# General_Switch_Board_V6.net
KiCad netlist of a schematic drawn in EAGLE
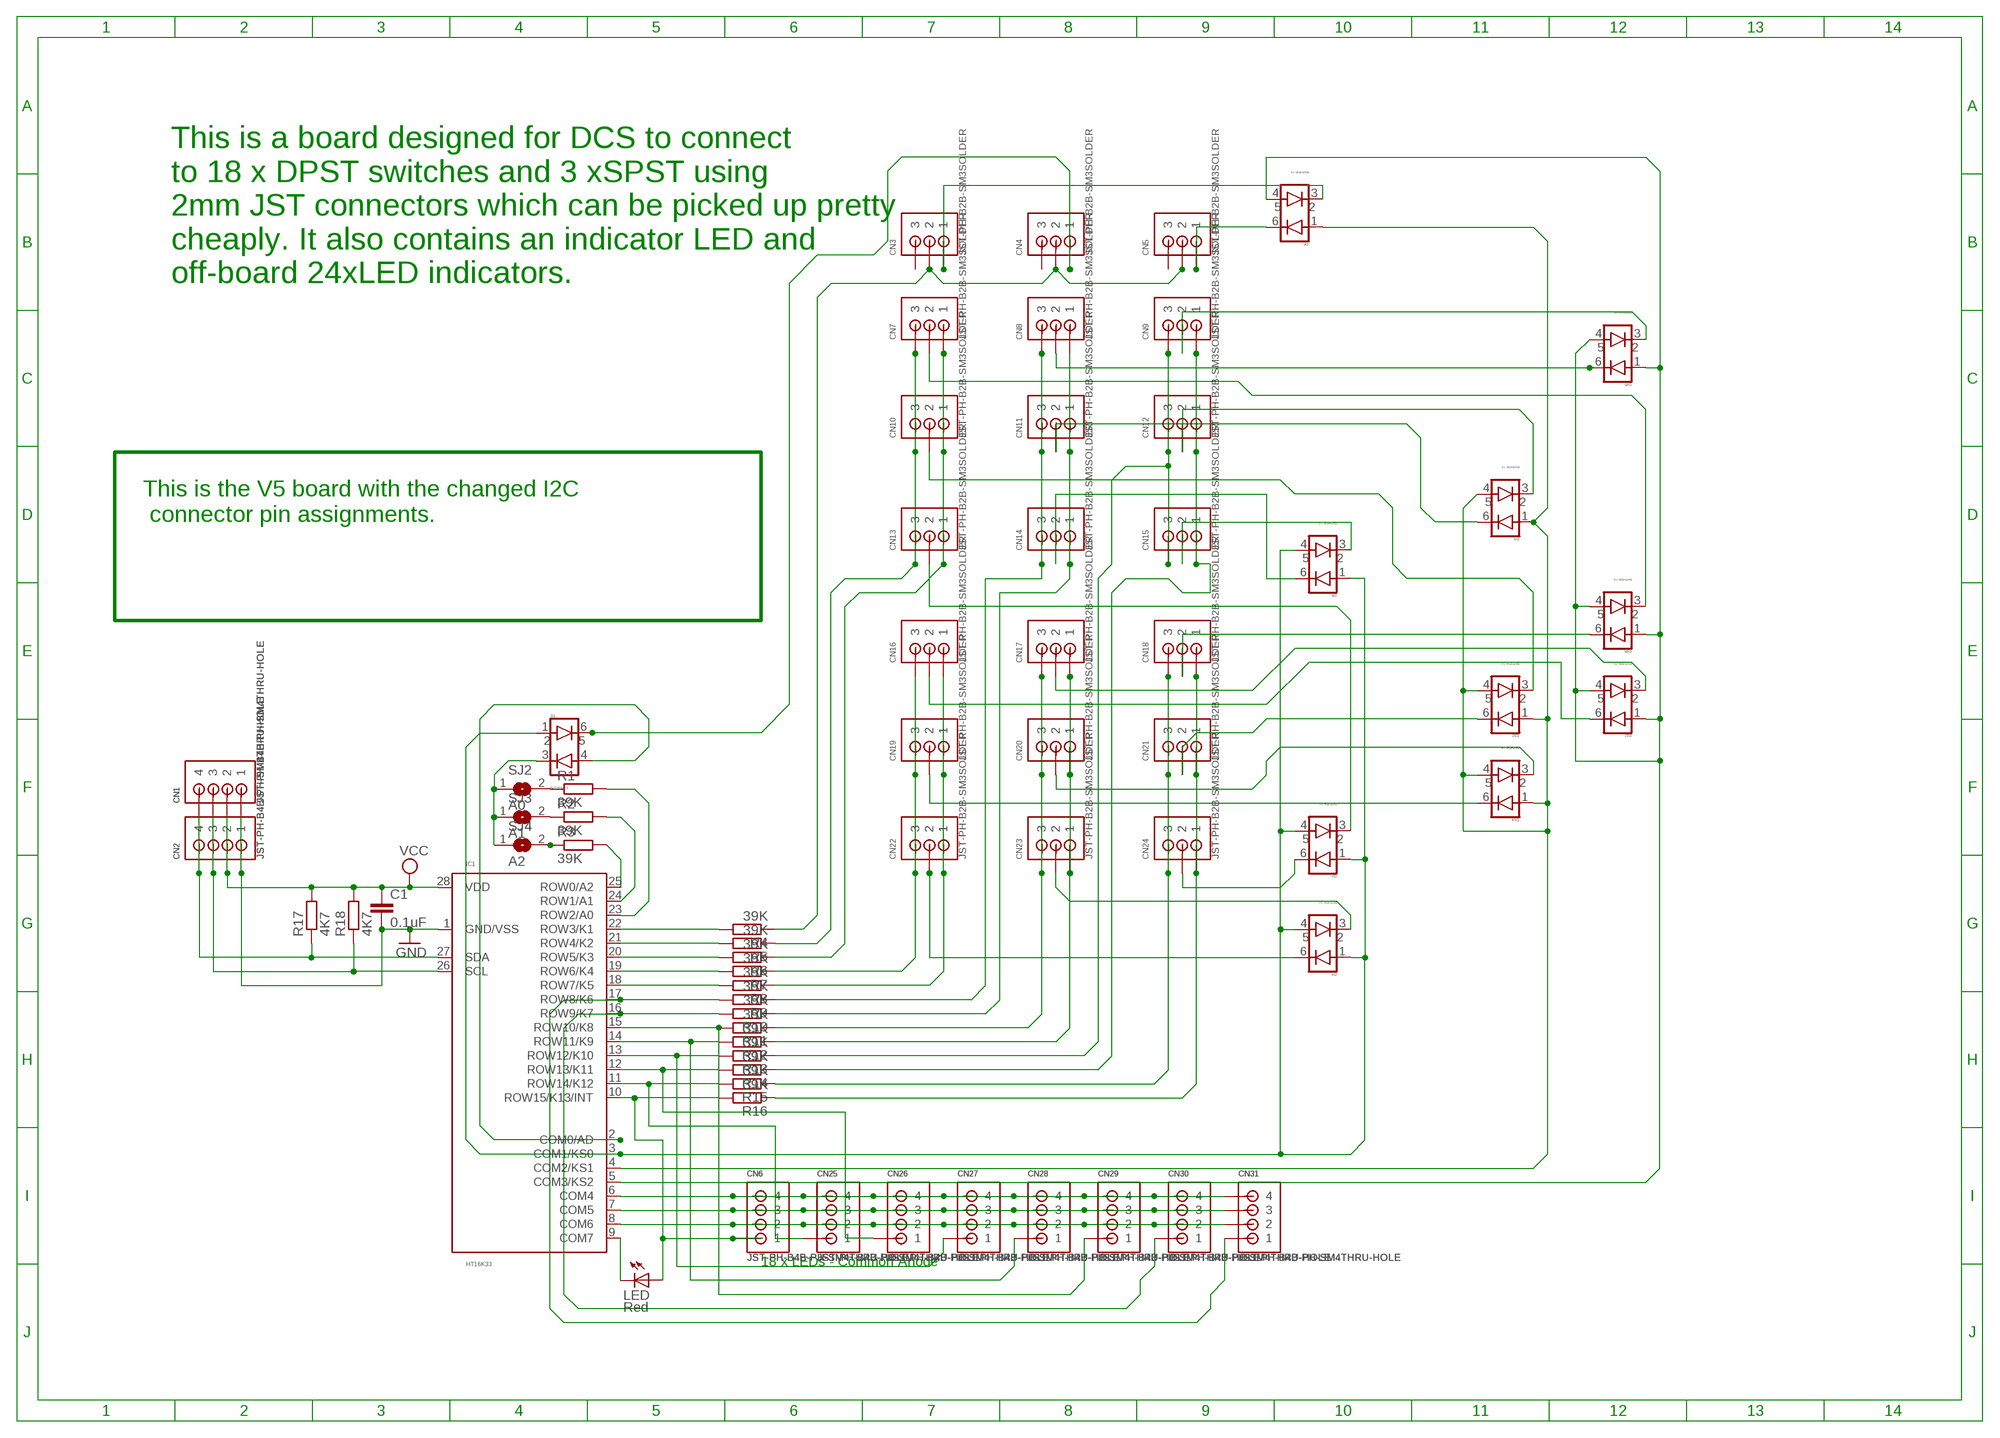
[diagram p0: schematic, sheet 1]

(export (version "E")
  (design (tool "Eeschema 10.0.6"))
  (components
    (comp (ref "C1")
      (value "0.1uF")
      (footprint "eagle-import:C0805")
      (libsource (lib "eagle-import") (part "C-EUC0805"))
    )
    (comp (ref "CN1")
      (value "JST-PH-B4B-PH-SM4THRU-HOLE")
      (footprint "eagle-import:B4B-PH-SOLDER")
      (libsource (lib "eagle-import") (part "JST-PH-B4B-PH-SM4THRU-HOLE"))
    )
    (comp (ref "CN2")
      (value "JST-PH-B4B-PH-SM4THRU-HOLE")
      (footprint "eagle-import:B4B-PH-SOLDER")
      (libsource (lib "eagle-import") (part "JST-PH-B4B-PH-SM4THRU-HOLE"))
    )
    (comp (ref "CN3")
      (value "JST-PH-B2B-SM3SOLDER")
      (footprint "eagle-import:B3B-PH-SOLDER")
      (libsource (lib "eagle-import") (part "JST-PH-B2B-SM3SOLDER"))
    )
    (comp (ref "CN4")
      (value "JST-PH-B2B-SM3SOLDER")
      (footprint "eagle-import:B3B-PH-SOLDER")
      (libsource (lib "eagle-import") (part "JST-PH-B2B-SM3SOLDER"))
    )
    (comp (ref "CN5")
      (value "JST-PH-B2B-SM3SOLDER")
      (footprint "eagle-import:B3B-PH-SOLDER")
      (libsource (lib "eagle-import") (part "JST-PH-B2B-SM3SOLDER"))
    )
    (comp (ref "CN6")
      (value "JST-PH-B4B-PH-SM4THRU-HOLE")
      (footprint "eagle-import:B4B-PH-SOLDER")
      (libsource (lib "eagle-import") (part "JST-PH-B4B-PH-SM4THRU-HOLE"))
    )
    (comp (ref "CN7")
      (value "JST-PH-B2B-SM3SOLDER")
      (footprint "eagle-import:B3B-PH-SOLDER")
      (libsource (lib "eagle-import") (part "JST-PH-B2B-SM3SOLDER"))
    )
    (comp (ref "CN8")
      (value "JST-PH-B2B-SM3SOLDER")
      (footprint "eagle-import:B3B-PH-SOLDER")
      (libsource (lib "eagle-import") (part "JST-PH-B2B-SM3SOLDER"))
    )
    (comp (ref "CN9")
      (value "JST-PH-B2B-SM3SOLDER")
      (footprint "eagle-import:B3B-PH-SOLDER")
      (libsource (lib "eagle-import") (part "JST-PH-B2B-SM3SOLDER"))
    )
    (comp (ref "CN10")
      (value "JST-PH-B2B-SM3SOLDER")
      (footprint "eagle-import:B3B-PH-SOLDER")
      (libsource (lib "eagle-import") (part "JST-PH-B2B-SM3SOLDER"))
    )
    (comp (ref "CN11")
      (value "JST-PH-B2B-SM3SOLDER")
      (footprint "eagle-import:B3B-PH-SOLDER")
      (libsource (lib "eagle-import") (part "JST-PH-B2B-SM3SOLDER"))
    )
    (comp (ref "CN12")
      (value "JST-PH-B2B-SM3SOLDER")
      (footprint "eagle-import:B3B-PH-SOLDER")
      (libsource (lib "eagle-import") (part "JST-PH-B2B-SM3SOLDER"))
    )
    (comp (ref "CN13")
      (value "JST-PH-B2B-SM3SOLDER")
      (footprint "eagle-import:B3B-PH-SOLDER")
      (libsource (lib "eagle-import") (part "JST-PH-B2B-SM3SOLDER"))
    )
    (comp (ref "CN14")
      (value "JST-PH-B2B-SM3SOLDER")
      (footprint "eagle-import:B3B-PH-SOLDER")
      (libsource (lib "eagle-import") (part "JST-PH-B2B-SM3SOLDER"))
    )
    (comp (ref "CN15")
      (value "JST-PH-B2B-SM3SOLDER")
      (footprint "eagle-import:B3B-PH-SOLDER")
      (libsource (lib "eagle-import") (part "JST-PH-B2B-SM3SOLDER"))
    )
    (comp (ref "CN16")
      (value "JST-PH-B2B-SM3SOLDER")
      (footprint "eagle-import:B3B-PH-SOLDER")
      (libsource (lib "eagle-import") (part "JST-PH-B2B-SM3SOLDER"))
    )
    (comp (ref "CN17")
      (value "JST-PH-B2B-SM3SOLDER")
      (footprint "eagle-import:B3B-PH-SOLDER")
      (libsource (lib "eagle-import") (part "JST-PH-B2B-SM3SOLDER"))
    )
    (comp (ref "CN18")
      (value "JST-PH-B2B-SM3SOLDER")
      (footprint "eagle-import:B3B-PH-SOLDER")
      (libsource (lib "eagle-import") (part "JST-PH-B2B-SM3SOLDER"))
    )
    (comp (ref "CN19")
      (value "JST-PH-B2B-SM3SOLDER")
      (footprint "eagle-import:B3B-PH-SOLDER")
      (libsource (lib "eagle-import") (part "JST-PH-B2B-SM3SOLDER"))
    )
    (comp (ref "CN20")
      (value "JST-PH-B2B-SM3SOLDER")
      (footprint "eagle-import:B3B-PH-SOLDER")
      (libsource (lib "eagle-import") (part "JST-PH-B2B-SM3SOLDER"))
    )
    (comp (ref "CN21")
      (value "JST-PH-B2B-SM3SOLDER")
      (footprint "eagle-import:B3B-PH-SOLDER")
      (libsource (lib "eagle-import") (part "JST-PH-B2B-SM3SOLDER"))
    )
    (comp (ref "CN22")
      (value "JST-PH-B2B-SM3SOLDER")
      (footprint "eagle-import:B3B-PH-SOLDER")
      (libsource (lib "eagle-import") (part "JST-PH-B2B-SM3SOLDER"))
    )
    (comp (ref "CN23")
      (value "JST-PH-B2B-SM3SOLDER")
      (footprint "eagle-import:B3B-PH-SOLDER")
      (libsource (lib "eagle-import") (part "JST-PH-B2B-SM3SOLDER"))
    )
    (comp (ref "CN24")
      (value "JST-PH-B2B-SM3SOLDER")
      (footprint "eagle-import:B3B-PH-SOLDER")
      (libsource (lib "eagle-import") (part "JST-PH-B2B-SM3SOLDER"))
    )
    (comp (ref "CN25")
      (value "JST-PH-B4B-PH-SM4THRU-HOLE")
      (footprint "eagle-import:B4B-PH-SOLDER")
      (libsource (lib "eagle-import") (part "JST-PH-B4B-PH-SM4THRU-HOLE"))
    )
    (comp (ref "CN26")
      (value "JST-PH-B4B-PH-SM4THRU-HOLE")
      (footprint "eagle-import:B4B-PH-SOLDER")
      (libsource (lib "eagle-import") (part "JST-PH-B4B-PH-SM4THRU-HOLE"))
    )
    (comp (ref "CN27")
      (value "JST-PH-B4B-PH-SM4THRU-HOLE")
      (footprint "eagle-import:B4B-PH-SOLDER")
      (libsource (lib "eagle-import") (part "JST-PH-B4B-PH-SM4THRU-HOLE"))
    )
    (comp (ref "CN28")
      (value "JST-PH-B4B-PH-SM4THRU-HOLE")
      (footprint "eagle-import:B4B-PH-SOLDER")
      (libsource (lib "eagle-import") (part "JST-PH-B4B-PH-SM4THRU-HOLE"))
    )
    (comp (ref "CN29")
      (value "JST-PH-B4B-PH-SM4THRU-HOLE")
      (footprint "eagle-import:B4B-PH-SOLDER")
      (libsource (lib "eagle-import") (part "JST-PH-B4B-PH-SM4THRU-HOLE"))
    )
    (comp (ref "CN30")
      (value "JST-PH-B4B-PH-SM4THRU-HOLE")
      (footprint "eagle-import:B4B-PH-SOLDER")
      (libsource (lib "eagle-import") (part "JST-PH-B4B-PH-SM4THRU-HOLE"))
    )
    (comp (ref "CN31")
      (value "JST-PH-B4B-PH-SM4THRU-HOLE")
      (footprint "eagle-import:B4B-PH-SOLDER")
      (libsource (lib "eagle-import") (part "JST-PH-B4B-PH-SM4THRU-HOLE"))
    )
    (comp (ref "D1")
      (value "BAT54TW-7-F")
      (footprint "eagle-import:SSOT6")
      (libsource (lib "eagle-import") (part "BAT54TW-7-F"))
    )
    (comp (ref "D2")
      (value "BAT54TW-7-F")
      (footprint "eagle-import:SSOT6")
      (libsource (lib "eagle-import") (part "BAT54TW-7-F"))
    )
    (comp (ref "D3")
      (value "BAT54TW-7-F")
      (footprint "eagle-import:SSOT6")
      (libsource (lib "eagle-import") (part "BAT54TW-7-F"))
    )
    (comp (ref "D4")
      (value "BAT54TW-7-F")
      (footprint "eagle-import:SSOT6")
      (libsource (lib "eagle-import") (part "BAT54TW-7-F"))
    )
    (comp (ref "D5")
      (value "BAT54TW-7-F")
      (footprint "eagle-import:SSOT6")
      (libsource (lib "eagle-import") (part "BAT54TW-7-F"))
    )
    (comp (ref "D6")
      (value "BAT54TW-7-F")
      (footprint "eagle-import:SSOT6")
      (libsource (lib "eagle-import") (part "BAT54TW-7-F"))
    )
    (comp (ref "D13")
      (value "BAT54TW-7-F")
      (footprint "eagle-import:SSOT6")
      (libsource (lib "eagle-import") (part "BAT54TW-7-F"))
    )
    (comp (ref "D14")
      (value "BAT54TW-7-F")
      (footprint "eagle-import:SSOT6")
      (libsource (lib "eagle-import") (part "BAT54TW-7-F"))
    )
    (comp (ref "D15")
      (value "BAT54TW-7-F")
      (footprint "eagle-import:SSOT6")
      (libsource (lib "eagle-import") (part "BAT54TW-7-F"))
    )
    (comp (ref "D16")
      (value "BAT54TW-7-F")
      (footprint "eagle-import:SSOT6")
      (libsource (lib "eagle-import") (part "BAT54TW-7-F"))
    )
    (comp (ref "D17")
      (value "BAT54TW-7-F")
      (footprint "eagle-import:SSOT6")
      (libsource (lib "eagle-import") (part "BAT54TW-7-F"))
    )
    (comp (ref "IC1")
      (value "HT16K33")
      (footprint "eagle-import:SOIC28")
      (libsource (lib "eagle-import") (part "HOLTEK_HT16K33"))
    )
    (comp (ref "LED")
      (value "Red")
      (footprint "eagle-import:CHIPLED_1206")
      (libsource (lib "eagle-import") (part "LEDCHIPLED_1206"))
    )
    (comp (ref "R1")
      (value "39K")
      (footprint "eagle-import:R0805")
      (libsource (lib "eagle-import") (part "resistor_R-EU_R0805"))
    )
    (comp (ref "R2")
      (value "39K")
      (footprint "eagle-import:R0805")
      (libsource (lib "eagle-import") (part "resistor_R-EU_R0805"))
    )
    (comp (ref "R3")
      (value "39K")
      (footprint "eagle-import:R0805")
      (libsource (lib "eagle-import") (part "resistor_R-EU_R0805"))
    )
    (comp (ref "R4")
      (value "39K")
      (footprint "eagle-import:R0805")
      (libsource (lib "eagle-import") (part "resistor_R-EU_R0805"))
    )
    (comp (ref "R5")
      (value "39K")
      (footprint "eagle-import:R0805")
      (libsource (lib "eagle-import") (part "resistor_R-EU_R0805"))
    )
    (comp (ref "R6")
      (value "39K")
      (footprint "eagle-import:R0805")
      (libsource (lib "eagle-import") (part "resistor_R-EU_R0805"))
    )
    (comp (ref "R7")
      (value "39K")
      (footprint "eagle-import:R0805")
      (libsource (lib "eagle-import") (part "resistor_R-EU_R0805"))
    )
    (comp (ref "R8")
      (value "39K")
      (footprint "eagle-import:R0805")
      (libsource (lib "eagle-import") (part "resistor_R-EU_R0805"))
    )
    (comp (ref "R9")
      (value "39K")
      (footprint "eagle-import:R0805")
      (libsource (lib "eagle-import") (part "resistor_R-EU_R0805"))
    )
    (comp (ref "R10")
      (value "39K")
      (footprint "eagle-import:R0805")
      (libsource (lib "eagle-import") (part "resistor_R-EU_R0805"))
    )
    (comp (ref "R11")
      (value "39K")
      (footprint "eagle-import:R0805")
      (libsource (lib "eagle-import") (part "resistor_R-EU_R0805"))
    )
    (comp (ref "R12")
      (value "39K")
      (footprint "eagle-import:R0805")
      (libsource (lib "eagle-import") (part "resistor_R-EU_R0805"))
    )
    (comp (ref "R13")
      (value "39K")
      (footprint "eagle-import:R0805")
      (libsource (lib "eagle-import") (part "resistor_R-EU_R0805"))
    )
    (comp (ref "R14")
      (value "39K")
      (footprint "eagle-import:R0805")
      (libsource (lib "eagle-import") (part "resistor_R-EU_R0805"))
    )
    (comp (ref "R15")
      (value "39K")
      (footprint "eagle-import:R0805")
      (libsource (lib "eagle-import") (part "resistor_R-EU_R0805"))
    )
    (comp (ref "R16")
      (value "39K")
      (footprint "eagle-import:R0805")
      (libsource (lib "eagle-import") (part "resistor_R-EU_R0805"))
    )
    (comp (ref "R17")
      (value "4K7")
      (footprint "eagle-import:R0805")
      (libsource (lib "eagle-import") (part "R-EU_R0805"))
    )
    (comp (ref "R18")
      (value "4K7")
      (footprint "eagle-import:R0805")
      (libsource (lib "eagle-import") (part "R-EU_R0805"))
    )
    (comp (ref "SJ2") (value "A0") (footprint "eagle-import:SJ") (libsource (lib "eagle-import") (part "SJ")))
    (comp (ref "SJ3") (value "A1") (footprint "eagle-import:SJ") (libsource (lib "eagle-import") (part "SJ")))
    (comp (ref "SJ4") (value "A2") (footprint "eagle-import:SJ") (libsource (lib "eagle-import") (part "SJ")))
  )
  (nets
    (net (code "1") (name "GND") (class "Default")
      (node (ref "C1") (pin "2") (pinfunction "2_2") (pintype "passive"))
      (node (ref "CN1") (pin "P1") (pinfunction "1_P1") (pintype "passive"))
      (node (ref "CN2") (pin "P1") (pinfunction "1_P1") (pintype "passive"))
      (node (ref "IC1") (pin "1") (pinfunction "GND/VSS_1") (pintype "power_in"))
    )
    (net (code "2") (name "Net-(CN1-3)") (class "Default")
      (node (ref "CN1") (pin "P3") (pinfunction "3_P3") (pintype "passive"))
      (node (ref "CN2") (pin "P3") (pinfunction "3_P3") (pintype "passive"))
      (node (ref "IC1") (pin "26") (pinfunction "SCL_26") (pintype "bidirectional"))
      (node (ref "R18") (pin "1") (pinfunction "1_1") (pintype "passive"))
    )
    (net (code "3") (name "Net-(CN1-4)") (class "Default")
      (node (ref "CN1") (pin "P4") (pinfunction "4_P4") (pintype "passive"))
      (node (ref "CN2") (pin "P4") (pinfunction "4_P4") (pintype "passive"))
      (node (ref "IC1") (pin "27") (pinfunction "SDA_27") (pintype "bidirectional"))
      (node (ref "R17") (pin "1") (pinfunction "1_1") (pintype "passive"))
    )
    (net (code "4") (name "Net-(CN3-1)") (class "Default")
      (node (ref "CN3") (pin "P1") (pinfunction "1_P1") (pintype "passive"))
      (node (ref "D6") (pin "3") (pinfunction "C2_3") (pintype "output"))
    )
    (net (code "5") (name "Net-(CN3-2)") (class "Default")
      (node (ref "CN3") (pin "P2") (pinfunction "2_P2") (pintype "passive"))
      (node (ref "CN4") (pin "P2") (pinfunction "2_P2") (pintype "passive"))
      (node (ref "CN5") (pin "P2") (pinfunction "2_P2") (pintype "passive"))
      (node (ref "R4") (pin "1") (pinfunction "1_1") (pintype "passive"))
    )
    (net (code "6") (name "Net-(CN4-1)") (class "Default")
      (node (ref "CN4") (pin "P1") (pinfunction "1_P1") (pintype "passive"))
      (node (ref "D1") (pin "6") (pinfunction "C1_6") (pintype "output"))
    )
    (net (code "7") (name "Net-(CN5-1)") (class "Default")
      (node (ref "CN5") (pin "P1") (pinfunction "1_P1") (pintype "passive"))
      (node (ref "D6") (pin "6") (pinfunction "C1_6") (pintype "output"))
    )
    (net (code "8") (name "Net-(CN6-1)") (class "Default")
      (node (ref "CN6") (pin "P1") (pinfunction "1_P1") (pintype "passive"))
      (node (ref "IC1") (pin "10") (pinfunction "ROW15/K13/INT_10") (pintype "input"))
      (node (ref "LED") (pin "A") (pinfunction "A_A") (pintype "passive"))
      (node (ref "R16") (pin "2") (pinfunction "2_2") (pintype "passive"))
    )
    (net (code "9") (name "Net-(CN7-2)") (class "Default")
      (node (ref "CN7") (pin "P2") (pinfunction "2_P2") (pintype "passive"))
      (node (ref "D16") (pin "3") (pinfunction "C2_3") (pintype "output"))
    )
    (net (code "10") (name "Net-(CN8-2)") (class "Default")
      (node (ref "CN8") (pin "P2") (pinfunction "2_P2") (pintype "passive"))
      (node (ref "D15") (pin "6") (pinfunction "C1_6") (pintype "output"))
    )
    (net (code "11") (name "Net-(CN9-2)") (class "Default")
      (node (ref "CN9") (pin "P2") (pinfunction "2_P2") (pintype "passive"))
      (node (ref "D15") (pin "3") (pinfunction "C2_3") (pintype "output"))
    )
    (net (code "12") (name "Net-(CN10-1)") (class "Default")
      (node (ref "CN10") (pin "P1") (pinfunction "1_P1") (pintype "passive"))
      (node (ref "CN13") (pin "P1") (pinfunction "1_P1") (pintype "passive"))
      (node (ref "CN7") (pin "P1") (pinfunction "1_P1") (pintype "passive"))
      (node (ref "R6") (pin "1") (pinfunction "1_1") (pintype "passive"))
    )
    (net (code "13") (name "Net-(CN10-2)") (class "Default")
      (node (ref "CN10") (pin "P2") (pinfunction "2_P2") (pintype "passive"))
      (node (ref "D13") (pin "3") (pinfunction "C2_3") (pintype "output"))
    )
    (net (code "14") (name "Net-(CN10-3)") (class "Default")
      (node (ref "CN10") (pin "P3") (pinfunction "3_P3") (pintype "passive"))
      (node (ref "CN13") (pin "P3") (pinfunction "3_P3") (pintype "passive"))
      (node (ref "CN7") (pin "P3") (pinfunction "3_P3") (pintype "passive"))
      (node (ref "R5") (pin "1") (pinfunction "1_1") (pintype "passive"))
    )
    (net (code "15") (name "Net-(CN11-1)") (class "Default")
      (node (ref "CN11") (pin "P1") (pinfunction "1_P1") (pintype "passive"))
      (node (ref "CN14") (pin "P1") (pinfunction "1_P1") (pintype "passive"))
      (node (ref "CN8") (pin "P1") (pinfunction "1_P1") (pintype "passive"))
      (node (ref "R10") (pin "1") (pinfunction "1_1") (pintype "passive"))
    )
    (net (code "16") (name "Net-(CN11-2)") (class "Default")
      (node (ref "CN11") (pin "P2") (pinfunction "2_P2") (pintype "passive"))
      (node (ref "D4") (pin "6") (pinfunction "C1_6") (pintype "output"))
    )
    (net (code "17") (name "Net-(CN11-3)") (class "Default")
      (node (ref "CN11") (pin "P3") (pinfunction "3_P3") (pintype "passive"))
      (node (ref "CN14") (pin "P3") (pinfunction "3_P3") (pintype "passive"))
      (node (ref "CN8") (pin "P3") (pinfunction "3_P3") (pintype "passive"))
      (node (ref "R9") (pin "1") (pinfunction "1_1") (pintype "passive"))
    )
    (net (code "18") (name "Net-(CN12-1)") (class "Default")
      (node (ref "CN12") (pin "P1") (pinfunction "1_P1") (pintype "passive"))
      (node (ref "CN15") (pin "P1") (pinfunction "1_P1") (pintype "passive"))
      (node (ref "CN9") (pin "P1") (pinfunction "1_P1") (pintype "passive"))
      (node (ref "R14") (pin "1") (pinfunction "1_1") (pintype "passive"))
    )
    (net (code "19") (name "Net-(CN12-2)") (class "Default")
      (node (ref "CN12") (pin "P2") (pinfunction "2_P2") (pintype "passive"))
      (node (ref "D4") (pin "3") (pinfunction "C2_3") (pintype "output"))
    )
    (net (code "20") (name "Net-(CN12-3)") (class "Default")
      (node (ref "CN12") (pin "P3") (pinfunction "3_P3") (pintype "passive"))
      (node (ref "CN15") (pin "P3") (pinfunction "3_P3") (pintype "passive"))
      (node (ref "CN9") (pin "P3") (pinfunction "3_P3") (pintype "passive"))
      (node (ref "R13") (pin "1") (pinfunction "1_1") (pintype "passive"))
    )
    (net (code "21") (name "Net-(CN13-2)") (class "Default")
      (node (ref "CN13") (pin "P2") (pinfunction "2_P2") (pintype "passive"))
      (node (ref "D2") (pin "3") (pinfunction "C2_3") (pintype "output"))
    )
    (net (code "22") (name "Net-(CN14-2)") (class "Default")
      (node (ref "CN14") (pin "P2") (pinfunction "2_P2") (pintype "passive"))
      (node (ref "D5") (pin "6") (pinfunction "C1_6") (pintype "output"))
    )
    (net (code "23") (name "Net-(CN15-2)") (class "Default")
      (node (ref "CN15") (pin "P2") (pinfunction "2_P2") (pintype "passive"))
      (node (ref "D5") (pin "3") (pinfunction "C2_3") (pintype "output"))
    )
    (net (code "24") (name "Net-(CN16-1)") (class "Default")
      (node (ref "CN16") (pin "P1") (pinfunction "1_P1") (pintype "passive"))
      (node (ref "CN19") (pin "P1") (pinfunction "1_P1") (pintype "passive"))
      (node (ref "CN22") (pin "P1") (pinfunction "1_P1") (pintype "passive"))
      (node (ref "R8") (pin "1") (pinfunction "1_1") (pintype "passive"))
    )
    (net (code "25") (name "Net-(CN16-2)") (class "Default")
      (node (ref "CN16") (pin "P2") (pinfunction "2_P2") (pintype "passive"))
      (node (ref "D17") (pin "6") (pinfunction "C1_6") (pintype "output"))
    )
    (net (code "26") (name "Net-(CN16-3)") (class "Default")
      (node (ref "CN16") (pin "P3") (pinfunction "3_P3") (pintype "passive"))
      (node (ref "CN19") (pin "P3") (pinfunction "3_P3") (pintype "passive"))
      (node (ref "CN22") (pin "P3") (pinfunction "3_P3") (pintype "passive"))
      (node (ref "R7") (pin "1") (pinfunction "1_1") (pintype "passive"))
    )
    (net (code "27") (name "Net-(CN17-1)") (class "Default")
      (node (ref "CN17") (pin "P1") (pinfunction "1_P1") (pintype "passive"))
      (node (ref "CN20") (pin "P1") (pinfunction "1_P1") (pintype "passive"))
      (node (ref "CN23") (pin "P1") (pinfunction "1_P1") (pintype "passive"))
      (node (ref "R12") (pin "1") (pinfunction "1_1") (pintype "passive"))
    )
    (net (code "28") (name "Net-(CN17-2)") (class "Default")
      (node (ref "CN17") (pin "P2") (pinfunction "2_P2") (pintype "passive"))
      (node (ref "D17") (pin "3") (pinfunction "C2_3") (pintype "output"))
    )
    (net (code "29") (name "Net-(CN17-3)") (class "Default")
      (node (ref "CN17") (pin "P3") (pinfunction "3_P3") (pintype "passive"))
      (node (ref "CN20") (pin "P3") (pinfunction "3_P3") (pintype "passive"))
      (node (ref "CN23") (pin "P3") (pinfunction "3_P3") (pintype "passive"))
      (node (ref "R11") (pin "1") (pinfunction "1_1") (pintype "passive"))
    )
    (net (code "30") (name "Net-(CN18-1)") (class "Default")
      (node (ref "CN18") (pin "P1") (pinfunction "1_P1") (pintype "passive"))
      (node (ref "CN21") (pin "P1") (pinfunction "1_P1") (pintype "passive"))
      (node (ref "CN24") (pin "P1") (pinfunction "1_P1") (pintype "passive"))
      (node (ref "R16") (pin "1") (pinfunction "1_1") (pintype "passive"))
    )
    (net (code "31") (name "Net-(CN18-2)") (class "Default")
      (node (ref "CN18") (pin "P2") (pinfunction "2_P2") (pintype "passive"))
      (node (ref "D16") (pin "6") (pinfunction "C1_6") (pintype "output"))
    )
    (net (code "32") (name "Net-(CN18-3)") (class "Default")
      (node (ref "CN18") (pin "P3") (pinfunction "3_P3") (pintype "passive"))
      (node (ref "CN21") (pin "P3") (pinfunction "3_P3") (pintype "passive"))
      (node (ref "CN24") (pin "P3") (pinfunction "3_P3") (pintype "passive"))
      (node (ref "R15") (pin "1") (pinfunction "1_1") (pintype "passive"))
    )
    (net (code "33") (name "Net-(CN19-2)") (class "Default")
      (node (ref "CN19") (pin "P2") (pinfunction "2_P2") (pintype "passive"))
      (node (ref "D14") (pin "6") (pinfunction "C1_6") (pintype "output"))
    )
    (net (code "34") (name "Net-(CN20-2)") (class "Default")
      (node (ref "CN20") (pin "P2") (pinfunction "2_P2") (pintype "passive"))
      (node (ref "D14") (pin "3") (pinfunction "C2_3") (pintype "output"))
    )
    (net (code "35") (name "Net-(CN21-2)") (class "Default")
      (node (ref "CN21") (pin "P2") (pinfunction "2_P2") (pintype "passive"))
      (node (ref "D13") (pin "6") (pinfunction "C1_6") (pintype "output"))
    )
    (net (code "36") (name "Net-(CN22-2)") (class "Default")
      (node (ref "CN22") (pin "P2") (pinfunction "2_P2") (pintype "passive"))
      (node (ref "D3") (pin "6") (pinfunction "C1_6") (pintype "output"))
    )
    (net (code "37") (name "Net-(CN23-2)") (class "Default")
      (node (ref "CN23") (pin "P2") (pinfunction "2_P2") (pintype "passive"))
      (node (ref "D3") (pin "3") (pinfunction "C2_3") (pintype "output"))
    )
    (net (code "38") (name "Net-(CN24-2)") (class "Default")
      (node (ref "CN24") (pin "P2") (pinfunction "2_P2") (pintype "passive"))
      (node (ref "D2") (pin "6") (pinfunction "C1_6") (pintype "output"))
    )
    (net (code "39") (name "Net-(CN25-1)") (class "Default")
      (node (ref "CN25") (pin "P1") (pinfunction "1_P1") (pintype "passive"))
      (node (ref "IC1") (pin "11") (pinfunction "ROW14/K12_11") (pintype "input"))
      (node (ref "R15") (pin "2") (pinfunction "2_2") (pintype "passive"))
    )
    (net (code "40") (name "Net-(CN25-2)") (class "Default")
      (node (ref "CN25") (pin "P2") (pinfunction "2_P2") (pintype "passive"))
      (node (ref "CN26") (pin "P2") (pinfunction "2_P2") (pintype "passive"))
      (node (ref "CN27") (pin "P2") (pinfunction "2_P2") (pintype "passive"))
      (node (ref "CN28") (pin "P2") (pinfunction "2_P2") (pintype "passive"))
      (node (ref "CN29") (pin "P2") (pinfunction "2_P2") (pintype "passive"))
      (node (ref "CN30") (pin "P2") (pinfunction "2_P2") (pintype "passive"))
      (node (ref "CN31") (pin "P2") (pinfunction "2_P2") (pintype "passive"))
      (node (ref "CN6") (pin "P2") (pinfunction "2_P2") (pintype "passive"))
      (node (ref "IC1") (pin "8") (pinfunction "COM6_8") (pintype "input"))
    )
    (net (code "41") (name "Net-(CN25-3)") (class "Default")
      (node (ref "CN25") (pin "P3") (pinfunction "3_P3") (pintype "passive"))
      (node (ref "CN26") (pin "P3") (pinfunction "3_P3") (pintype "passive"))
      (node (ref "CN27") (pin "P3") (pinfunction "3_P3") (pintype "passive"))
      (node (ref "CN28") (pin "P3") (pinfunction "3_P3") (pintype "passive"))
      (node (ref "CN29") (pin "P3") (pinfunction "3_P3") (pintype "passive"))
      (node (ref "CN30") (pin "P3") (pinfunction "3_P3") (pintype "passive"))
      (node (ref "CN31") (pin "P3") (pinfunction "3_P3") (pintype "passive"))
      (node (ref "CN6") (pin "P3") (pinfunction "3_P3") (pintype "passive"))
      (node (ref "IC1") (pin "7") (pinfunction "COM5_7") (pintype "input"))
    )
    (net (code "42") (name "Net-(CN25-4)") (class "Default")
      (node (ref "CN25") (pin "P4") (pinfunction "4_P4") (pintype "passive"))
      (node (ref "CN26") (pin "P4") (pinfunction "4_P4") (pintype "passive"))
      (node (ref "CN27") (pin "P4") (pinfunction "4_P4") (pintype "passive"))
      (node (ref "CN28") (pin "P4") (pinfunction "4_P4") (pintype "passive"))
      (node (ref "CN29") (pin "P4") (pinfunction "4_P4") (pintype "passive"))
      (node (ref "CN30") (pin "P4") (pinfunction "4_P4") (pintype "passive"))
      (node (ref "CN31") (pin "P4") (pinfunction "4_P4") (pintype "passive"))
      (node (ref "CN6") (pin "P4") (pinfunction "4_P4") (pintype "passive"))
      (node (ref "IC1") (pin "6") (pinfunction "COM4_6") (pintype "input"))
    )
    (net (code "43") (name "Net-(CN26-1)") (class "Default")
      (node (ref "CN26") (pin "P1") (pinfunction "1_P1") (pintype "passive"))
      (node (ref "IC1") (pin "12") (pinfunction "ROW13/K11_12") (pintype "input"))
      (node (ref "R14") (pin "2") (pinfunction "2_2") (pintype "passive"))
    )
    (net (code "44") (name "Net-(CN27-1)") (class "Default")
      (node (ref "CN27") (pin "P1") (pinfunction "1_P1") (pintype "passive"))
      (node (ref "IC1") (pin "13") (pinfunction "ROW12/K10_13") (pintype "input"))
      (node (ref "R13") (pin "2") (pinfunction "2_2") (pintype "passive"))
    )
    (net (code "45") (name "Net-(CN28-1)") (class "Default")
      (node (ref "CN28") (pin "P1") (pinfunction "1_P1") (pintype "passive"))
      (node (ref "IC1") (pin "14") (pinfunction "ROW11/K9_14") (pintype "input"))
      (node (ref "R12") (pin "2") (pinfunction "2_2") (pintype "passive"))
    )
    (net (code "46") (name "Net-(CN29-1)") (class "Default")
      (node (ref "CN29") (pin "P1") (pinfunction "1_P1") (pintype "passive"))
      (node (ref "IC1") (pin "15") (pinfunction "ROW10/K8_15") (pintype "input"))
      (node (ref "R11") (pin "2") (pinfunction "2_2") (pintype "passive"))
    )
    (net (code "47") (name "Net-(CN30-1)") (class "Default")
      (node (ref "CN30") (pin "P1") (pinfunction "1_P1") (pintype "passive"))
      (node (ref "IC1") (pin "16") (pinfunction "ROW9/K7_16") (pintype "bidirectional"))
      (node (ref "R10") (pin "2") (pinfunction "2_2") (pintype "passive"))
    )
    (net (code "48") (name "Net-(CN31-1)") (class "Default")
      (node (ref "CN31") (pin "P1") (pinfunction "1_P1") (pintype "passive"))
      (node (ref "IC1") (pin "17") (pinfunction "ROW8/K6_17") (pintype "input"))
      (node (ref "R9") (pin "2") (pinfunction "2_2") (pintype "passive"))
    )
    (net (code "49") (name "Net-(D1-A1)") (class "Default")
      (node (ref "D1") (pin "1") (pinfunction "A1_1") (pintype "input"))
      (node (ref "D2") (pin "1") (pinfunction "A1_1") (pintype "input"))
      (node (ref "D2") (pin "4") (pinfunction "A2_4") (pintype "input"))
      (node (ref "D3") (pin "1") (pinfunction "A1_1") (pintype "input"))
      (node (ref "D3") (pin "4") (pinfunction "A2_4") (pintype "input"))
      (node (ref "D5") (pin "1") (pinfunction "A1_1") (pintype "input"))
      (node (ref "D5") (pin "4") (pinfunction "A2_4") (pintype "input"))
      (node (ref "IC1") (pin "3") (pinfunction "COM1/KS0_3") (pintype "input"))
    )
    (net (code "50") (name "Net-(D1-A2)") (class "Default")
      (node (ref "D1") (pin "4") (pinfunction "A2_4") (pintype "input"))
      (node (ref "IC1") (pin "2") (pinfunction "COM0/AD_2") (pintype "input"))
    )
    (net (code "51") (name "Net-(D1-C2)") (class "Default")
      (node (ref "D1") (pin "3") (pinfunction "C2_3") (pintype "output"))
      (node (ref "SJ2") (pin "1") (pinfunction "1_1") (pintype "passive"))
      (node (ref "SJ3") (pin "1") (pinfunction "1_1") (pintype "passive"))
      (node (ref "SJ4") (pin "1") (pinfunction "1_1") (pintype "passive"))
    )
    (net (code "52") (name "Net-(D13-A1)") (class "Default")
      (node (ref "D13") (pin "1") (pinfunction "A1_1") (pintype "input"))
      (node (ref "D13") (pin "4") (pinfunction "A2_4") (pintype "input"))
      (node (ref "D14") (pin "1") (pinfunction "A1_1") (pintype "input"))
      (node (ref "D14") (pin "4") (pinfunction "A2_4") (pintype "input"))
      (node (ref "D4") (pin "1") (pinfunction "A1_1") (pintype "input"))
      (node (ref "D4") (pin "4") (pinfunction "A2_4") (pintype "input"))
      (node (ref "D6") (pin "1") (pinfunction "A1_1") (pintype "input"))
      (node (ref "IC1") (pin "4") (pinfunction "COM2/KS1_4") (pintype "input"))
    )
    (net (code "53") (name "Net-(D15-A1)") (class "Default")
      (node (ref "D15") (pin "1") (pinfunction "A1_1") (pintype "input"))
      (node (ref "D15") (pin "4") (pinfunction "A2_4") (pintype "input"))
      (node (ref "D16") (pin "1") (pinfunction "A1_1") (pintype "input"))
      (node (ref "D16") (pin "4") (pinfunction "A2_4") (pintype "input"))
      (node (ref "D17") (pin "1") (pinfunction "A1_1") (pintype "input"))
      (node (ref "D17") (pin "4") (pinfunction "A2_4") (pintype "input"))
      (node (ref "D6") (pin "4") (pinfunction "A2_4") (pintype "input"))
      (node (ref "IC1") (pin "5") (pinfunction "COM3/KS2_5") (pintype "input"))
    )
    (net (code "54") (name "Net-(IC1-COM7)") (class "Default")
      (node (ref "IC1") (pin "9") (pinfunction "COM7_9") (pintype "input"))
      (node (ref "LED") (pin "C") (pinfunction "C_C") (pintype "passive"))
    )
    (net (code "55") (name "Net-(IC1-ROW0{slash}A2)") (class "Default")
      (node (ref "IC1") (pin "25") (pinfunction "ROW0/A2_25") (pintype "bidirectional"))
      (node (ref "R3") (pin "2") (pinfunction "2_2") (pintype "passive"))
    )
    (net (code "56") (name "Net-(IC1-ROW1{slash}A1)") (class "Default")
      (node (ref "IC1") (pin "24") (pinfunction "ROW1/A1_24") (pintype "bidirectional"))
      (node (ref "R2") (pin "2") (pinfunction "2_2") (pintype "passive"))
    )
    (net (code "57") (name "Net-(IC1-ROW2{slash}A0)") (class "Default")
      (node (ref "IC1") (pin "23") (pinfunction "ROW2/A0_23") (pintype "bidirectional"))
      (node (ref "R1") (pin "2") (pinfunction "2_2") (pintype "passive"))
    )
    (net (code "58") (name "Net-(IC1-ROW3{slash}K1)") (class "Default")
      (node (ref "IC1") (pin "22") (pinfunction "ROW3/K1_22") (pintype "bidirectional"))
      (node (ref "R4") (pin "2") (pinfunction "2_2") (pintype "passive"))
    )
    (net (code "59") (name "Net-(IC1-ROW4{slash}K2)") (class "Default")
      (node (ref "IC1") (pin "21") (pinfunction "ROW4/K2_21") (pintype "input"))
      (node (ref "R5") (pin "2") (pinfunction "2_2") (pintype "passive"))
    )
    (net (code "60") (name "Net-(IC1-ROW5{slash}K3)") (class "Default")
      (node (ref "IC1") (pin "20") (pinfunction "ROW5/K3_20") (pintype "bidirectional"))
      (node (ref "R6") (pin "2") (pinfunction "2_2") (pintype "passive"))
    )
    (net (code "61") (name "Net-(IC1-ROW6{slash}K4)") (class "Default")
      (node (ref "IC1") (pin "19") (pinfunction "ROW6/K4_19") (pintype "bidirectional"))
      (node (ref "R7") (pin "2") (pinfunction "2_2") (pintype "passive"))
    )
    (net (code "62") (name "Net-(IC1-ROW7{slash}K5)") (class "Default")
      (node (ref "IC1") (pin "18") (pinfunction "ROW7/K5_18") (pintype "bidirectional"))
      (node (ref "R8") (pin "2") (pinfunction "2_2") (pintype "passive"))
    )
    (net (code "63") (name "Net-(R1-Pad1)") (class "Default")
      (node (ref "R1") (pin "1") (pinfunction "1_1") (pintype "passive"))
      (node (ref "SJ2") (pin "2") (pinfunction "2_2") (pintype "passive"))
    )
    (net (code "64") (name "Net-(R2-Pad1)") (class "Default")
      (node (ref "R2") (pin "1") (pinfunction "1_1") (pintype "passive"))
      (node (ref "SJ3") (pin "2") (pinfunction "2_2") (pintype "passive"))
    )
    (net (code "65") (name "Net-(R3-Pad1)") (class "Default")
      (node (ref "R3") (pin "1") (pinfunction "1_1") (pintype "passive"))
      (node (ref "SJ4") (pin "2") (pinfunction "2_2") (pintype "passive"))
    )
    (net (code "66") (name "VCC") (class "Default")
      (node (ref "C1") (pin "1") (pinfunction "1_1") (pintype "passive"))
      (node (ref "CN1") (pin "P2") (pinfunction "2_P2") (pintype "passive"))
      (node (ref "CN2") (pin "P2") (pinfunction "2_P2") (pintype "passive"))
      (node (ref "IC1") (pin "28") (pinfunction "VDD_28") (pintype "power_in"))
      (node (ref "R17") (pin "2") (pinfunction "2_2") (pintype "passive"))
      (node (ref "R18") (pin "2") (pinfunction "2_2") (pintype "passive"))
    )
    (net (code "67") (name "unconnected-(CN3-3-PadP3)") (class "Default")
      (node (ref "CN3") (pin "P3") (pinfunction "3_P3") (pintype "passive"))
    )
    (net (code "68") (name "unconnected-(CN4-3-PadP3)") (class "Default")
      (node (ref "CN4") (pin "P3") (pinfunction "3_P3") (pintype "passive"))
    )
    (net (code "69") (name "unconnected-(CN5-3-PadP3)") (class "Default")
      (node (ref "CN5") (pin "P3") (pinfunction "3_P3") (pintype "passive"))
    )
    (net (code "70") (name "unconnected-(D1-NC0-Pad2)") (class "Default")
      (node (ref "D1") (pin "2") (pinfunction "NC0_2") (pintype "no_connect"))
    )
    (net (code "71") (name "unconnected-(D1-NC1-Pad5)") (class "Default")
      (node (ref "D1") (pin "5") (pinfunction "NC1_5") (pintype "no_connect"))
    )
    (net (code "72") (name "unconnected-(D2-NC0-Pad2)") (class "Default")
      (node (ref "D2") (pin "2") (pinfunction "NC0_2") (pintype "no_connect"))
    )
    (net (code "73") (name "unconnected-(D2-NC1-Pad5)") (class "Default")
      (node (ref "D2") (pin "5") (pinfunction "NC1_5") (pintype "no_connect"))
    )
    (net (code "74") (name "unconnected-(D3-NC0-Pad2)") (class "Default")
      (node (ref "D3") (pin "2") (pinfunction "NC0_2") (pintype "no_connect"))
    )
    (net (code "75") (name "unconnected-(D3-NC1-Pad5)") (class "Default")
      (node (ref "D3") (pin "5") (pinfunction "NC1_5") (pintype "no_connect"))
    )
    (net (code "76") (name "unconnected-(D4-NC0-Pad2)") (class "Default")
      (node (ref "D4") (pin "2") (pinfunction "NC0_2") (pintype "no_connect"))
    )
    (net (code "77") (name "unconnected-(D4-NC1-Pad5)") (class "Default")
      (node (ref "D4") (pin "5") (pinfunction "NC1_5") (pintype "no_connect"))
    )
    (net (code "78") (name "unconnected-(D5-NC0-Pad2)") (class "Default")
      (node (ref "D5") (pin "2") (pinfunction "NC0_2") (pintype "no_connect"))
    )
    (net (code "79") (name "unconnected-(D5-NC1-Pad5)") (class "Default")
      (node (ref "D5") (pin "5") (pinfunction "NC1_5") (pintype "no_connect"))
    )
    (net (code "80") (name "unconnected-(D6-NC0-Pad2)") (class "Default")
      (node (ref "D6") (pin "2") (pinfunction "NC0_2") (pintype "no_connect"))
    )
    (net (code "81") (name "unconnected-(D6-NC1-Pad5)") (class "Default")
      (node (ref "D6") (pin "5") (pinfunction "NC1_5") (pintype "no_connect"))
    )
    (net (code "82") (name "unconnected-(D13-NC0-Pad2)") (class "Default")
      (node (ref "D13") (pin "2") (pinfunction "NC0_2") (pintype "no_connect"))
    )
    (net (code "83") (name "unconnected-(D13-NC1-Pad5)") (class "Default")
      (node (ref "D13") (pin "5") (pinfunction "NC1_5") (pintype "no_connect"))
    )
    (net (code "84") (name "unconnected-(D14-NC0-Pad2)") (class "Default")
      (node (ref "D14") (pin "2") (pinfunction "NC0_2") (pintype "no_connect"))
    )
    (net (code "85") (name "unconnected-(D14-NC1-Pad5)") (class "Default")
      (node (ref "D14") (pin "5") (pinfunction "NC1_5") (pintype "no_connect"))
    )
    (net (code "86") (name "unconnected-(D15-NC0-Pad2)") (class "Default")
      (node (ref "D15") (pin "2") (pinfunction "NC0_2") (pintype "no_connect"))
    )
    (net (code "87") (name "unconnected-(D15-NC1-Pad5)") (class "Default")
      (node (ref "D15") (pin "5") (pinfunction "NC1_5") (pintype "no_connect"))
    )
    (net (code "88") (name "unconnected-(D16-NC0-Pad2)") (class "Default")
      (node (ref "D16") (pin "2") (pinfunction "NC0_2") (pintype "no_connect"))
    )
    (net (code "89") (name "unconnected-(D16-NC1-Pad5)") (class "Default")
      (node (ref "D16") (pin "5") (pinfunction "NC1_5") (pintype "no_connect"))
    )
    (net (code "90") (name "unconnected-(D17-NC0-Pad2)") (class "Default")
      (node (ref "D17") (pin "2") (pinfunction "NC0_2") (pintype "no_connect"))
    )
    (net (code "91") (name "unconnected-(D17-NC1-Pad5)") (class "Default")
      (node (ref "D17") (pin "5") (pinfunction "NC1_5") (pintype "no_connect"))
    )
  )
)
